# Ethernet.net
KiCad netlist of a schematic drawn in Altium Designer
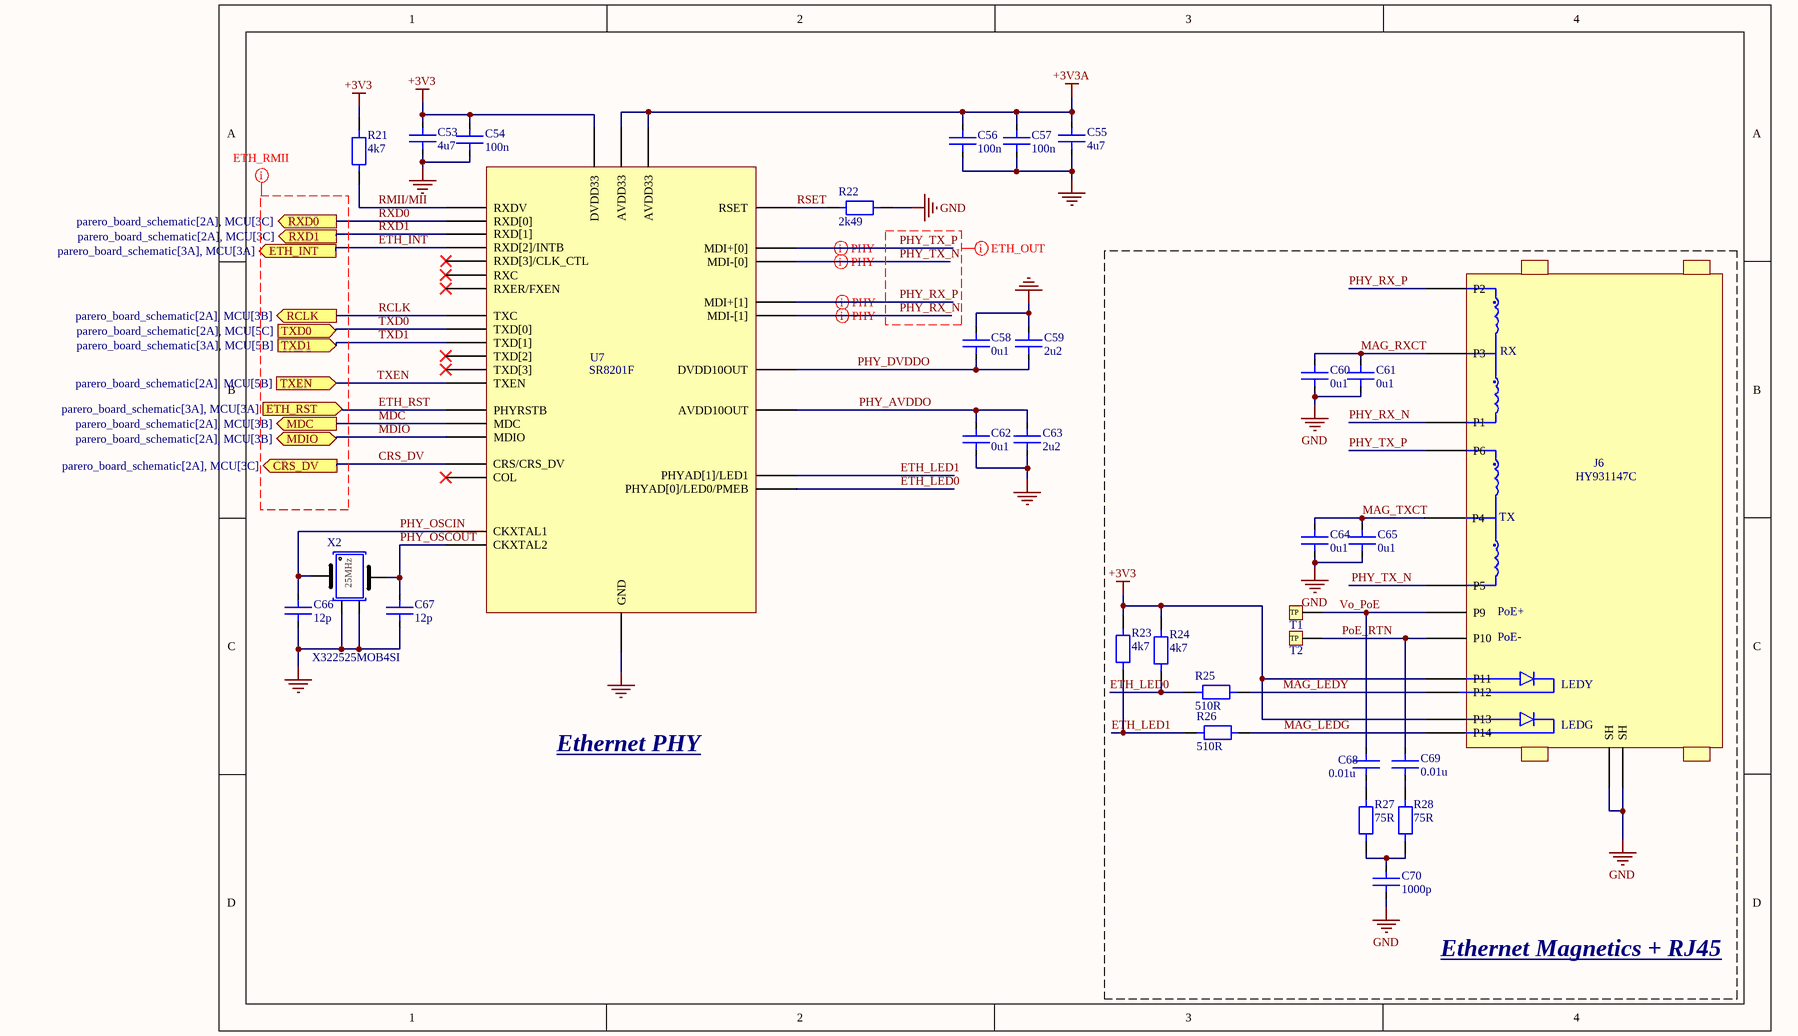
[diagram p0: Ethernet.SchDoc]

(export (version "E")
  (design (tool "Eeschema 10.0.6"))
  (components
    (comp (ref "C53")
      (value "4u7")
      (footprint "CAP_MLCC_0603")
      (description "Multilayer  Ceramic Capacitor")
      (libsource (lib "conics_libs") (part "Cap MLCC 0603"))
    )
    (comp (ref "C54")
      (value "100n")
      (footprint "CAP_MLCC_0402")
      (description "Multilayer  Ceramic Capacitor")
      (libsource (lib "conics_libs") (part "Cap MLCC 0402"))
    )
    (comp (ref "C55")
      (value "4u7")
      (footprint "CAP_MLCC_0603")
      (description "Multilayer  Ceramic Capacitor")
      (libsource (lib "conics_libs") (part "Cap MLCC 0603"))
    )
    (comp (ref "C56")
      (value "100n")
      (footprint "CAP_MLCC_0402")
      (description "Multilayer  Ceramic Capacitor")
      (libsource (lib "conics_libs") (part "Cap MLCC 0402"))
    )
    (comp (ref "C57")
      (value "100n")
      (footprint "CAP_MLCC_0402")
      (description "Multilayer  Ceramic Capacitor")
      (libsource (lib "conics_libs") (part "Cap MLCC 0402"))
    )
    (comp (ref "C58")
      (value "0u1")
      (footprint "CAP_MLCC_0402")
      (description "Multilayer  Ceramic Capacitor")
      (libsource (lib "conics_libs") (part "Cap MLCC 0402"))
    )
    (comp (ref "C59")
      (value "2u2")
      (footprint "CAP_MLCC_0402")
      (description "Multilayer  Ceramic Capacitor")
      (libsource (lib "conics_libs") (part "Cap MLCC 0402"))
    )
    (comp (ref "C60")
      (value "0u1")
      (footprint "CAP_MLCC_0402")
      (description "Multilayer  Ceramic Capacitor")
      (libsource (lib "conics_libs") (part "Cap MLCC 0402"))
    )
    (comp (ref "C61")
      (value "0u1")
      (footprint "CAP_MLCC_0402")
      (description "Multilayer  Ceramic Capacitor")
      (libsource (lib "conics_libs") (part "Cap MLCC 0402"))
    )
    (comp (ref "C62")
      (value "0u1")
      (footprint "CAP_MLCC_0402")
      (description "Multilayer  Ceramic Capacitor")
      (libsource (lib "conics_libs") (part "Cap MLCC 0402"))
    )
    (comp (ref "C63")
      (value "2u2")
      (footprint "CAP_MLCC_0402")
      (description "Multilayer  Ceramic Capacitor")
      (libsource (lib "conics_libs") (part "Cap MLCC 0402"))
    )
    (comp (ref "C64")
      (value "0u1")
      (footprint "CAP_MLCC_0402")
      (description "Multilayer  Ceramic Capacitor")
      (libsource (lib "conics_libs") (part "Cap MLCC 0402"))
    )
    (comp (ref "C65")
      (value "0u1")
      (footprint "CAP_MLCC_0402")
      (description "Multilayer  Ceramic Capacitor")
      (libsource (lib "conics_libs") (part "Cap MLCC 0402"))
    )
    (comp (ref "C66")
      (value "12p")
      (footprint "CAP_MLCC_0402")
      (description "Multilayer  Ceramic Capacitor")
      (libsource (lib "conics_libs") (part "Cap MLCC 0402"))
    )
    (comp (ref "C67")
      (value "12p")
      (footprint "CAP_MLCC_0402")
      (description "Multilayer  Ceramic Capacitor")
      (libsource (lib "conics_libs") (part "Cap MLCC 0402"))
    )
    (comp (ref "C68")
      (value "0.01u")
      (footprint "CAP_MLCC_0402")
      (description "Multilayer  Ceramic Capacitor")
      (libsource (lib "conics_libs") (part "Cap MLCC 0402"))
    )
    (comp (ref "C69")
      (value "0.01u")
      (footprint "CAP_MLCC_0402")
      (description "Multilayer  Ceramic Capacitor")
      (libsource (lib "conics_libs") (part "Cap MLCC 0402"))
    )
    (comp (ref "C70")
      (value "1000p")
      (footprint "CAP_MLCC_0402")
      (description "Multilayer  Ceramic Capacitor")
      (libsource (lib "conics_libs") (part "Cap MLCC 0402"))
    )
    (comp (ref "J6")
      (value "HY931147C")
      (footprint "CONN_ETH_RJ45")
      (description "1 With LED Through Hole Modular/Ethernet Connector Jacks With Magnetics RoHS")
      (libsource (lib "conics_libs") (part "Connector RJ45 MagJack"))
    )
    (comp (ref "R21")
      (value "4k7")
      (footprint "RES_SMD_0402")
      (description "General Purpose SMD Carbon Resistor")
      (libsource (lib "conics_libs") (part "Resistor 0402"))
    )
    (comp (ref "R22")
      (value "2k49")
      (footprint "RES_SMD_0402")
      (description "General Purpose SMD Carbon Resistor")
      (libsource (lib "conics_libs") (part "Resistor 0402"))
    )
    (comp (ref "R23")
      (value "4k7")
      (footprint "RES_SMD_0402")
      (description "General Purpose SMD Carbon Resistor")
      (libsource (lib "conics_libs") (part "Resistor 0402"))
    )
    (comp (ref "R24")
      (value "4k7")
      (footprint "RES_SMD_0402")
      (description "General Purpose SMD Carbon Resistor")
      (libsource (lib "conics_libs") (part "Resistor 0402"))
    )
    (comp (ref "R25")
      (value "510R")
      (footprint "RES_SMD_0402")
      (description "General Purpose SMD Carbon Resistor")
      (libsource (lib "conics_libs") (part "Resistor 0402"))
    )
    (comp (ref "R26")
      (value "510R")
      (footprint "RES_SMD_0402")
      (description "General Purpose SMD Carbon Resistor")
      (libsource (lib "conics_libs") (part "Resistor 0402"))
    )
    (comp (ref "R27")
      (value "75R")
      (footprint "RES_SMD_0402")
      (description "General Purpose SMD Carbon Resistor")
      (libsource (lib "conics_libs") (part "Resistor 0402"))
    )
    (comp (ref "R28")
      (value "75R")
      (footprint "RES_SMD_0402")
      (description "General Purpose SMD Carbon Resistor")
      (libsource (lib "conics_libs") (part "Resistor 0402"))
    )
    (comp (ref "T1")
      (value "TP")
      (footprint "TPAD")
      (description "Test Pad")
      (libsource (lib "conics_libs") (part "Tpad"))
    )
    (comp (ref "T2")
      (value "TP")
      (footprint "TPAD")
      (description "Test Pad")
      (libsource (lib "conics_libs") (part "Tpad"))
    )
    (comp (ref "U7")
      (value "SR8201F")
      (footprint "SR8201F_QFN32")
      (description "Single-chip 10/100M Ethernet PHYceiver, supporting Auto MDIX")
      (libsource (lib "conics_libs") (part "Interface ETHERNET PHY SR8201F"))
    )
    (comp (ref "X2")
      (value "X322525MOB4SI")
      (footprint "XTAL_SMD_YXC")
      (description "Crystal Oscillator 12pF SMD3225-4P Crystals ROHS")
      (libsource (lib "conics_libs") (part "Crystal SMD 25MHz"))
    )
  )
  (nets
    (net (code "1") (name "+3V3") (class "Default")
      (node (ref "C53") (pin "2") (pintype "passive"))
      (node (ref "C54") (pin "2") (pintype "passive"))
      (node (ref "J6") (pin "11") (pinfunction "P11_11") (pintype "passive"))
      (node (ref "J6") (pin "13") (pinfunction "P13_13") (pintype "passive"))
      (node (ref "R21") (pin "2") (pintype "passive"))
      (node (ref "R23") (pin "2") (pintype "passive"))
      (node (ref "R24") (pin "2") (pintype "passive"))
      (node (ref "U7") (pin "14") (pinfunction "DVDD33_14") (pintype "passive"))
    )
    (net (code "2") (name "+3V3A") (class "Default")
      (node (ref "C55") (pin "2") (pintype "passive"))
      (node (ref "C56") (pin "2") (pintype "passive"))
      (node (ref "C57") (pin "2") (pintype "passive"))
      (node (ref "U7") (pin "30") (pinfunction "AVDD33_30") (pintype "passive"))
      (node (ref "U7") (pin "7") (pinfunction "AVDD33_7") (pintype "passive"))
    )
    (net (code "3") (name "/CRS_DV") (class "Default")
      (node (ref "U7") (pin "26") (pinfunction "CRS/CRS_DV_26") (pintype "passive"))
    )
    (net (code "4") (name "/ETH_INT") (class "Default")
      (node (ref "U7") (pin "11") (pinfunction "RXD[2]/INTB_11") (pintype "passive"))
    )
    (net (code "5") (name "/ETH_LED0") (class "Default")
      (node (ref "R24") (pin "1") (pintype "passive"))
      (node (ref "R25") (pin "1") (pintype "passive"))
      (node (ref "U7") (pin "24") (pinfunction "PHYAD[0]/LED0/PMEB_24") (pintype "passive"))
    )
    (net (code "6") (name "/ETH_LED1") (class "Default")
      (node (ref "R23") (pin "1") (pintype "passive"))
      (node (ref "R26") (pin "1") (pintype "passive"))
      (node (ref "U7") (pin "25") (pinfunction "PHYAD[1]/LED1_25") (pintype "passive"))
    )
    (net (code "7") (name "/ETH_RST") (class "Default")
      (node (ref "U7") (pin "21") (pinfunction "PHYRSTB_21") (pintype "passive"))
    )
    (net (code "8") (name "/MAG_LEDG") (class "Default")
      (node (ref "J6") (pin "14") (pinfunction "P14_14") (pintype "passive"))
      (node (ref "R26") (pin "2") (pintype "passive"))
    )
    (net (code "9") (name "/MAG_LEDY") (class "Default")
      (node (ref "J6") (pin "12") (pinfunction "P12_12") (pintype "passive"))
      (node (ref "R25") (pin "2") (pintype "passive"))
    )
    (net (code "10") (name "/MAG_RXCT") (class "Default")
      (node (ref "C60") (pin "2") (pintype "passive"))
      (node (ref "C61") (pin "2") (pintype "passive"))
      (node (ref "J6") (pin "3") (pinfunction "P3_3") (pintype "passive"))
    )
    (net (code "11") (name "/MAG_TXCT") (class "Default")
      (node (ref "C64") (pin "2") (pintype "passive"))
      (node (ref "C65") (pin "2") (pintype "passive"))
      (node (ref "J6") (pin "4") (pinfunction "P4_4") (pintype "passive"))
    )
    (net (code "12") (name "/MDC") (class "Default")
      (node (ref "U7") (pin "22") (pinfunction "MDC_22") (pintype "passive"))
    )
    (net (code "13") (name "/MDIO") (class "Default")
      (node (ref "U7") (pin "23") (pinfunction "MDIO_23") (pintype "passive"))
    )
    (net (code "14") (name "/PHY_AVDDO") (class "Default")
      (node (ref "C62") (pin "2") (pintype "passive"))
      (node (ref "C63") (pin "2") (pintype "passive"))
      (node (ref "U7") (pin "2") (pinfunction "AVDD10OUT_2") (pintype "passive"))
    )
    (net (code "15") (name "/PHY_DVDDO") (class "Default")
      (node (ref "C58") (pin "1") (pintype "passive"))
      (node (ref "C59") (pin "1") (pintype "passive"))
      (node (ref "U7") (pin "29") (pinfunction "DVDD10OUT_29") (pintype "passive"))
    )
    (net (code "16") (name "/PHY_OSCIN") (class "Default")
      (node (ref "C66") (pin "2") (pintype "passive"))
      (node (ref "U7") (pin "31") (pinfunction "CKXTAL1_31") (pintype "passive"))
      (node (ref "X2") (pin "1") (pintype "passive"))
    )
    (net (code "17") (name "/PHY_OSCOUT") (class "Default")
      (node (ref "C67") (pin "2") (pintype "passive"))
      (node (ref "U7") (pin "32") (pinfunction "CKXTAL2_32") (pintype "passive"))
      (node (ref "X2") (pin "3") (pintype "passive"))
    )
    (net (code "18") (name "/PHY_RX_N") (class "Default")
      (node (ref "J6") (pin "1") (pinfunction "P1_1") (pintype "passive"))
      (node (ref "U7") (pin "6") (pinfunction "MDI-[1]_6") (pintype "passive"))
    )
    (net (code "19") (name "/PHY_RX_P") (class "Default")
      (node (ref "J6") (pin "2") (pinfunction "P2_2") (pintype "passive"))
      (node (ref "U7") (pin "5") (pinfunction "MDI+[1]_5") (pintype "passive"))
    )
    (net (code "20") (name "/PHY_TX_N") (class "Default")
      (node (ref "J6") (pin "5") (pinfunction "P5_5") (pintype "passive"))
      (node (ref "U7") (pin "4") (pinfunction "MDI-[0]_4") (pintype "passive"))
    )
    (net (code "21") (name "/PHY_TX_P") (class "Default")
      (node (ref "J6") (pin "6") (pinfunction "P6_6") (pintype "passive"))
      (node (ref "U7") (pin "3") (pinfunction "MDI+[0]_3") (pintype "passive"))
    )
    (net (code "22") (name "/PoE_RTN") (class "Default")
      (node (ref "C69") (pin "2") (pintype "passive"))
      (node (ref "J6") (pin "10") (pinfunction "P10_10") (pintype "passive"))
      (node (ref "T2") (pin "1") (pinfunction "TP_1") (pintype "passive"))
    )
    (net (code "23") (name "/RCLK") (class "Default")
      (node (ref "U7") (pin "15") (pinfunction "TXC_15") (pintype "passive"))
    )
    (net (code "24") (name "/RMII{slash}MII") (class "Default")
      (node (ref "R21") (pin "1") (pintype "passive"))
      (node (ref "U7") (pin "8") (pinfunction "RXDV_8") (pintype "passive"))
    )
    (net (code "25") (name "/RSET") (class "Default")
      (node (ref "R22") (pin "1") (pintype "passive"))
      (node (ref "U7") (pin "1") (pinfunction "RSET_1") (pintype "passive"))
    )
    (net (code "26") (name "/RXD0") (class "Default")
      (node (ref "U7") (pin "9") (pinfunction "RXD[0]_9") (pintype "passive"))
    )
    (net (code "27") (name "/RXD1") (class "Default")
      (node (ref "U7") (pin "10") (pinfunction "RXD[1]_10") (pintype "passive"))
    )
    (net (code "28") (name "/TXD0") (class "Default")
      (node (ref "U7") (pin "16") (pinfunction "TXD[0]_16") (pintype "passive"))
    )
    (net (code "29") (name "/TXD1") (class "Default")
      (node (ref "U7") (pin "17") (pinfunction "TXD[1]_17") (pintype "passive"))
    )
    (net (code "30") (name "/TXEN") (class "Default")
      (node (ref "U7") (pin "20") (pinfunction "TXEN_20") (pintype "passive"))
    )
    (net (code "31") (name "/Vo_PoE") (class "Default")
      (node (ref "C68") (pin "2") (pintype "passive"))
      (node (ref "J6") (pin "9") (pinfunction "P9_9") (pintype "passive"))
      (node (ref "T1") (pin "1") (pinfunction "TP_1") (pintype "passive"))
    )
    (net (code "32") (name "GND") (class "Default")
      (node (ref "C53") (pin "1") (pintype "passive"))
      (node (ref "C54") (pin "1") (pintype "passive"))
      (node (ref "C55") (pin "1") (pintype "passive"))
      (node (ref "C56") (pin "1") (pintype "passive"))
      (node (ref "C57") (pin "1") (pintype "passive"))
      (node (ref "C58") (pin "2") (pintype "passive"))
      (node (ref "C59") (pin "2") (pintype "passive"))
      (node (ref "C60") (pin "1") (pintype "passive"))
      (node (ref "C61") (pin "1") (pintype "passive"))
      (node (ref "C62") (pin "1") (pintype "passive"))
      (node (ref "C63") (pin "1") (pintype "passive"))
      (node (ref "C64") (pin "1") (pintype "passive"))
      (node (ref "C65") (pin "1") (pintype "passive"))
      (node (ref "C66") (pin "1") (pintype "passive"))
      (node (ref "C67") (pin "1") (pintype "passive"))
      (node (ref "C70") (pin "1") (pintype "passive"))
      (node (ref "J6") (pin "15") (pinfunction "SH_15") (pintype "passive"))
      (node (ref "J6") (pin "16") (pinfunction "SH_16") (pintype "passive"))
      (node (ref "R22") (pin "2") (pintype "passive"))
      (node (ref "U7") (pin "33") (pinfunction "GND_33") (pintype "passive"))
      (node (ref "X2") (pin "2") (pintype "passive"))
      (node (ref "X2") (pin "4") (pintype "passive"))
    )
    (net (code "33") (name "Net-(C68-Pad1)") (class "Default")
      (node (ref "C68") (pin "1") (pintype "passive"))
      (node (ref "R27") (pin "2") (pintype "passive"))
    )
    (net (code "34") (name "Net-(C69-Pad1)") (class "Default")
      (node (ref "C69") (pin "1") (pintype "passive"))
      (node (ref "R28") (pin "2") (pintype "passive"))
    )
    (net (code "35") (name "Net-(C70-Pad2)") (class "Default")
      (node (ref "C70") (pin "2") (pintype "passive"))
      (node (ref "R27") (pin "1") (pintype "passive"))
      (node (ref "R28") (pin "1") (pintype "passive"))
    )
    (net (code "36") (name "unconnected-(U7-COL-Pad27)") (class "Default")
      (node (ref "U7") (pin "27") (pinfunction "COL_27") (pintype "passive+no_connect"))
    )
    (net (code "37") (name "unconnected-(U7-RXC-Pad13)") (class "Default")
      (node (ref "U7") (pin "13") (pinfunction "RXC_13") (pintype "passive+no_connect"))
    )
    (net (code "38") (name "unconnected-(U7-RXD[3]{slash}CLK_CTL-Pad12)") (class "Default")
      (node (ref "U7") (pin "12") (pinfunction "RXD[3]/CLK_CTL_12") (pintype "passive+no_connect"))
    )
    (net (code "39") (name "unconnected-(U7-RXER{slash}FXEN-Pad28)") (class "Default")
      (node (ref "U7") (pin "28") (pinfunction "RXER/FXEN_28") (pintype "passive+no_connect"))
    )
    (net (code "40") (name "unconnected-(U7-TXD[2]-Pad18)") (class "Default")
      (node (ref "U7") (pin "18") (pinfunction "TXD[2]_18") (pintype "passive+no_connect"))
    )
    (net (code "41") (name "unconnected-(U7-TXD[3]-Pad19)") (class "Default")
      (node (ref "U7") (pin "19") (pinfunction "TXD[3]_19") (pintype "passive+no_connect"))
    )
  )
)
